# motor_driver.net
KiCad netlist of a schematic drawn in Altium Designer
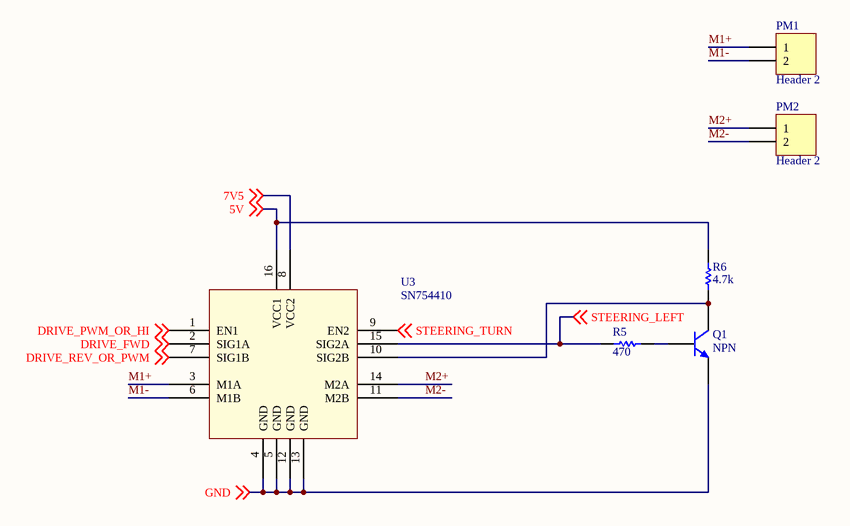
[diagram p0: motor_driver.SchDoc]

(export (version "E")
  (design (tool "Eeschema 10.0.6"))
  (components
    (comp (ref "PM1")
      (value "Header 2")
      (footprint "HDR1X2")
      (description "Header, 2-Pin")
      (fields (field (name "PUBLISHER") "Altium Limited"))
      (libsource (lib "Miscellaneous Connectors") (part "Header 2"))
    )
    (comp (ref "PM2")
      (value "Header 2")
      (footprint "HDR1X2")
      (description "Header, 2-Pin")
      (fields (field (name "PUBLISHER") "Altium Limited"))
      (libsource (lib "Miscellaneous Connectors") (part "Header 2"))
    )
    (comp (ref "Q1")
      (value "NPN")
      (footprint "SOT23")
      (description "NPN Bipolar Transistor")
      (fields (field (name "PUBLISHER") "Altium Limited"))
      (libsource (lib "Miscellaneous Devices") (part "NPN"))
    )
    (comp (ref "R5")
      (value "470")
      (footprint "0805-R")
      (description "Resistor")
      (fields (field (name "Comment") "Res1") (field (name "PUBLISHER") "Altium Limited"))
      (libsource (lib "Miscellaneous Devices") (part "Res1"))
    )
    (comp (ref "R6")
      (value "4.7k")
      (footprint "0805-R")
      (description "Resistor")
      (fields (field (name "Comment") "Res1") (field (name "PUBLISHER") "Altium Limited"))
      (libsource (lib "Miscellaneous Devices") (part "Res1"))
    )
    (comp (ref "U3") (value "SN754410") (footprint "DIP16") (libsource (lib "SN754410") (part "SN754410")))
  )
  (nets
    (net (code "1") (name "/M1+") (class "Default")
      (node (ref "PM1") (pin "1") (pinfunction "1_1") (pintype "passive"))
      (node (ref "U3") (pin "3") (pinfunction "M1A_3") (pintype "passive"))
    )
    (net (code "2") (name "/M1-") (class "Default")
      (node (ref "PM1") (pin "2") (pinfunction "2_2") (pintype "passive"))
      (node (ref "U3") (pin "6") (pinfunction "M1B_6") (pintype "passive"))
    )
    (net (code "3") (name "/M2+") (class "Default")
      (node (ref "PM2") (pin "1") (pinfunction "1_1") (pintype "passive"))
      (node (ref "U3") (pin "14") (pinfunction "M2A_14") (pintype "passive"))
    )
    (net (code "4") (name "/M2-") (class "Default")
      (node (ref "PM2") (pin "2") (pinfunction "2_2") (pintype "passive"))
      (node (ref "U3") (pin "11") (pinfunction "M2B_11") (pintype "passive"))
    )
    (net (code "5") (name "5V") (class "Default")
      (node (ref "R6") (pin "2") (pinfunction "2_2") (pintype "passive"))
      (node (ref "U3") (pin "16") (pinfunction "VCC1_16") (pintype "passive"))
    )
    (net (code "6") (name "7V5") (class "Default")
      (node (ref "U3") (pin "8") (pinfunction "VCC2_8") (pintype "passive"))
    )
    (net (code "7") (name "DRIVE_FWD") (class "Default")
      (node (ref "U3") (pin "2") (pinfunction "SIG1A_2") (pintype "passive"))
    )
    (net (code "8") (name "DRIVE_PWM_OR_HI") (class "Default")
      (node (ref "U3") (pin "1") (pinfunction "EN1_1") (pintype "passive"))
    )
    (net (code "9") (name "DRIVE_REV_OR_PWM") (class "Default")
      (node (ref "U3") (pin "7") (pinfunction "SIG1B_7") (pintype "passive"))
    )
    (net (code "10") (name "GND") (class "Default")
      (node (ref "Q1") (pin "3") (pinfunction "E_3") (pintype "passive"))
      (node (ref "U3") (pin "12") (pinfunction "GND_12") (pintype "passive"))
      (node (ref "U3") (pin "13") (pinfunction "GND_13") (pintype "passive"))
      (node (ref "U3") (pin "4") (pinfunction "GND_4") (pintype "passive"))
      (node (ref "U3") (pin "5") (pinfunction "GND_5") (pintype "passive"))
    )
    (net (code "11") (name "Net-(Q1-B)") (class "Default")
      (node (ref "Q1") (pin "2") (pinfunction "B_2") (pintype "passive"))
      (node (ref "R5") (pin "2") (pinfunction "2_2") (pintype "passive"))
    )
    (net (code "12") (name "Net-(Q1-C)") (class "Default")
      (node (ref "Q1") (pin "1") (pinfunction "C_1") (pintype "passive"))
      (node (ref "R6") (pin "1") (pinfunction "1_1") (pintype "passive"))
      (node (ref "U3") (pin "10") (pinfunction "SIG2B_10") (pintype "passive"))
    )
    (net (code "13") (name "STEERING_LEFT") (class "Default")
      (node (ref "R5") (pin "1") (pinfunction "1_1") (pintype "passive"))
      (node (ref "U3") (pin "15") (pinfunction "SIG2A_15") (pintype "passive"))
    )
    (net (code "14") (name "STEERING_TURN") (class "Default")
      (node (ref "U3") (pin "9") (pinfunction "EN2_9") (pintype "passive"))
    )
  )
)
